# darpa-power-distribution.net
KiCad netlist of a schematic drawn in EAGLE
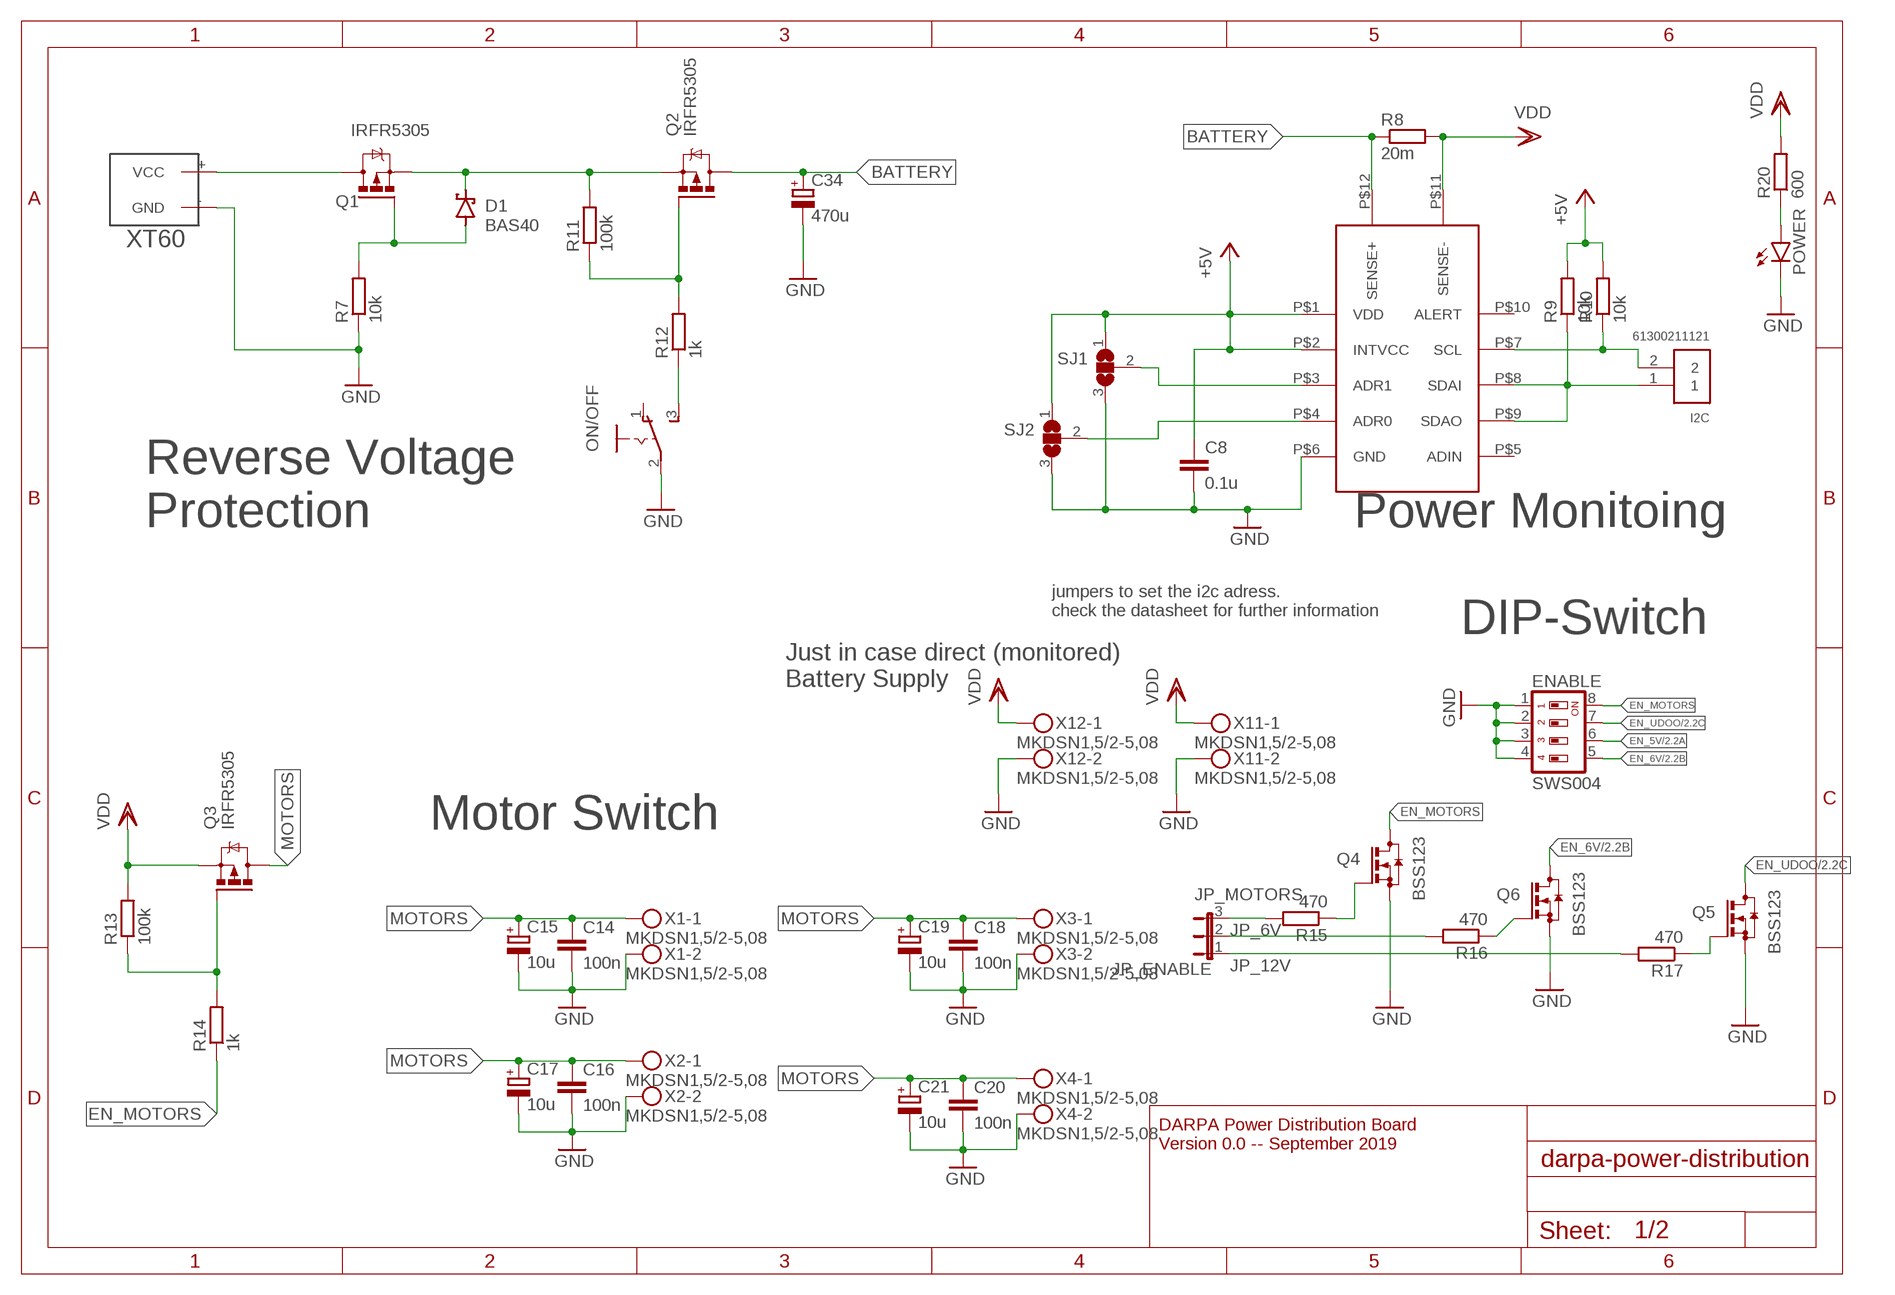
[diagram p0: schematic, sheet 1]
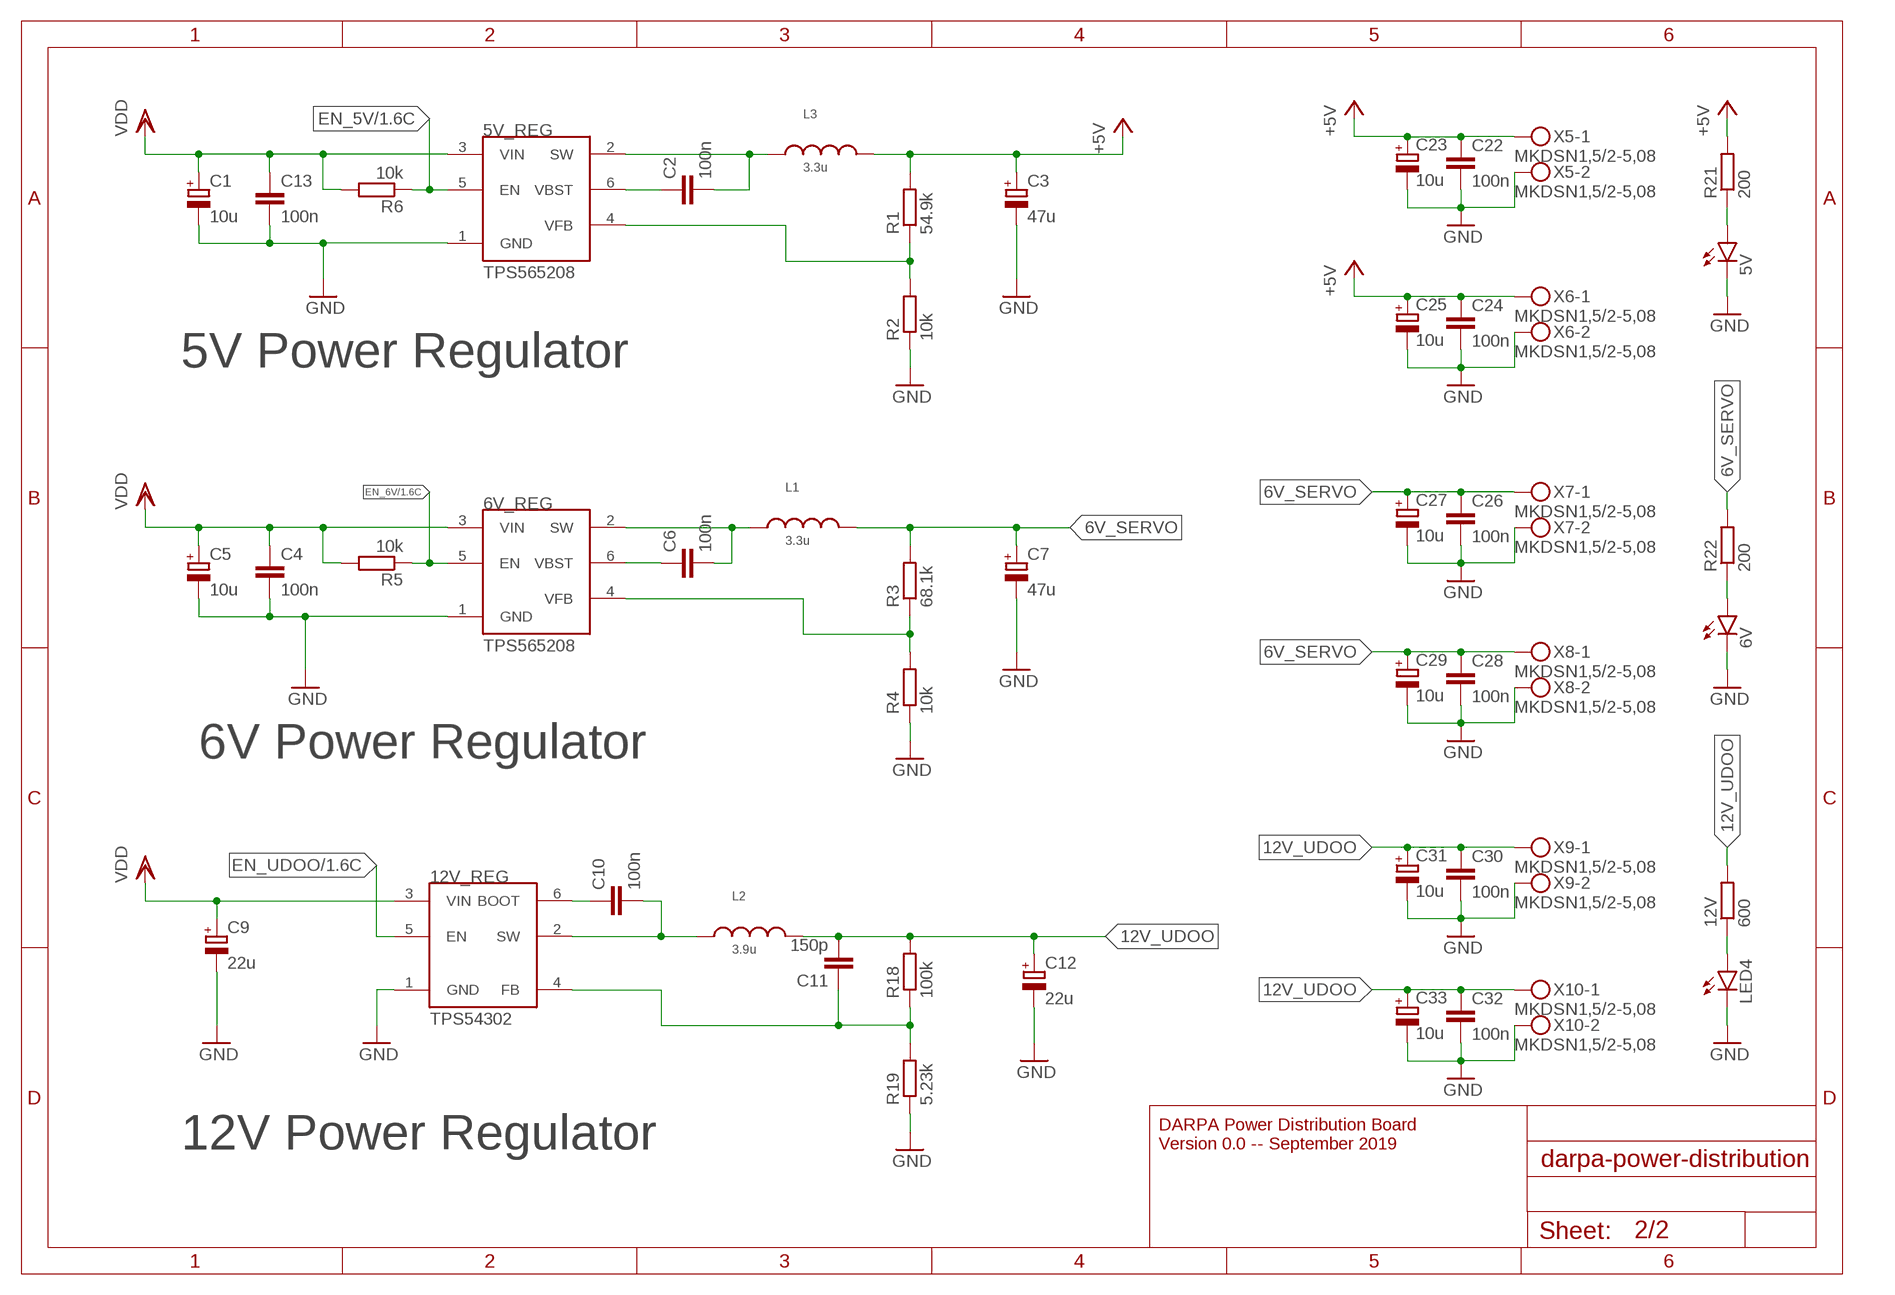
[diagram p1: schematic, sheet 2]

(export (version "E")
  (design (tool "Eeschema 10.0.6"))
  (components
    (comp (ref "C8")
      (value "0.1u")
      (footprint "eagle-import:C0805K")
      (libsource (lib "eagle-import") (part "C-EUC0805K"))
    )
    (comp (ref "C14")
      (value "100n")
      (footprint "eagle-import:C0805K")
      (libsource (lib "eagle-import") (part "C-EUC0805K"))
    )
    (comp (ref "C15")
      (value "10u")
      (footprint "eagle-import:E1,8-4")
      (libsource (lib "eagle-import") (part "CPOL-EUE1.8-4"))
    )
    (comp (ref "C16")
      (value "100n")
      (footprint "eagle-import:C0805K")
      (libsource (lib "eagle-import") (part "C-EUC0805K"))
    )
    (comp (ref "C17")
      (value "10u")
      (footprint "eagle-import:E1,8-4")
      (libsource (lib "eagle-import") (part "CPOL-EUE1.8-4"))
    )
    (comp (ref "C18")
      (value "100n")
      (footprint "eagle-import:C0805K")
      (libsource (lib "eagle-import") (part "C-EUC0805K"))
    )
    (comp (ref "C19")
      (value "10u")
      (footprint "eagle-import:E1,8-4")
      (libsource (lib "eagle-import") (part "CPOL-EUE1.8-4"))
    )
    (comp (ref "C20")
      (value "100n")
      (footprint "eagle-import:C0805K")
      (libsource (lib "eagle-import") (part "C-EUC0805K"))
    )
    (comp (ref "C21")
      (value "10u")
      (footprint "eagle-import:E1,8-4")
      (libsource (lib "eagle-import") (part "CPOL-EUE1.8-4"))
    )
    (comp (ref "C34")
      (value "470u")
      (footprint "eagle-import:E7,5-16")
      (libsource (lib "eagle-import") (part "CPOL-EUE7.5-16"))
    )
    (comp (ref "D1")
      (value "BAS40")
      (footprint "eagle-import:SOT23")
      (libsource (lib "eagle-import") (part "BAS40"))
    )
    (comp (ref "ENABLE")
      (value "SWS004")
      (footprint "eagle-import:SMS-004")
      (libsource (lib "eagle-import") (part "SWS004"))
    )
    (comp (ref "I2C")
      (value "61300211121")
      (footprint "eagle-import:61300211121")
      (fields
        (field (name "DIGI_KEY_PART_NUMBER") "732-5315-ND")
        (field (name "MANUFACTURER") "Wurth Electronics Inc.")
        (field (name "CREATED_BY") "PCBLayout.com")
      )
      (libsource (lib "eagle-import") (part "61300211121"))
    )
    (comp (ref "JP_ENABLE")
      (value "JP2E")
      (footprint "eagle-import:JP2")
      (libsource (lib "eagle-import") (part "JP2E"))
    )
    (comp (ref "ON/OFF")
      (value "M251")
      (footprint "eagle-import:M251")
      (libsource (lib "eagle-import") (part "M251"))
    )
    (comp (ref "POWER")
      (value "LEDSML0805")
      (footprint "eagle-import:SML0805")
      (libsource (lib "eagle-import") (part "LEDSML0805"))
    )
    (comp (ref "Q1")
      (value "IRFR5305")
      (footprint "eagle-import:D-PAK_TO252AA")
      (libsource (lib "eagle-import") (part "IRF?5305R"))
    )
    (comp (ref "Q2")
      (value "IRFR5305")
      (footprint "eagle-import:D-PAK_TO252AA")
      (libsource (lib "eagle-import") (part "IRF?5305R"))
    )
    (comp (ref "Q3")
      (value "IRFR5305")
      (footprint "eagle-import:D-PAK_TO252AA")
      (libsource (lib "eagle-import") (part "IRF?5305R"))
    )
    (comp (ref "Q4")
      (value "BSS123")
      (footprint "eagle-import:SOT23")
      (libsource (lib "eagle-import") (part "BSS123"))
    )
    (comp (ref "Q5")
      (value "BSS123")
      (footprint "eagle-import:SOT23")
      (libsource (lib "eagle-import") (part "BSS123"))
    )
    (comp (ref "Q6")
      (value "BSS123")
      (footprint "eagle-import:SOT23")
      (libsource (lib "eagle-import") (part "BSS123"))
    )
    (comp (ref "R7")
      (value "10k")
      (footprint "eagle-import:R0805")
      (libsource (lib "eagle-import") (part "R-EU_R0805"))
    )
    (comp (ref "R8")
      (value "20m")
      (footprint "eagle-import:P0613_15")
      (libsource (lib "eagle-import") (part "R-EU_0613/15"))
    )
    (comp (ref "R9")
      (value "10k")
      (footprint "eagle-import:R0805")
      (libsource (lib "eagle-import") (part "R-EU_R0805"))
    )
    (comp (ref "R10")
      (value "10k")
      (footprint "eagle-import:R0805")
      (libsource (lib "eagle-import") (part "R-EU_R0805"))
    )
    (comp (ref "R11")
      (value "100k")
      (footprint "eagle-import:R0805")
      (libsource (lib "eagle-import") (part "R-EU_R0805"))
    )
    (comp (ref "R12")
      (value "1k")
      (footprint "eagle-import:R0805")
      (libsource (lib "eagle-import") (part "R-EU_R0805"))
    )
    (comp (ref "R13")
      (value "100k")
      (footprint "eagle-import:R0805")
      (libsource (lib "eagle-import") (part "R-EU_R0805"))
    )
    (comp (ref "R14")
      (value "1k")
      (footprint "eagle-import:R0805")
      (libsource (lib "eagle-import") (part "R-EU_R0805"))
    )
    (comp (ref "R15")
      (value "470")
      (footprint "eagle-import:R0805")
      (libsource (lib "eagle-import") (part "R-EU_R0805"))
    )
    (comp (ref "R16")
      (value "470")
      (footprint "eagle-import:R0805")
      (libsource (lib "eagle-import") (part "R-EU_R0805"))
    )
    (comp (ref "R17")
      (value "470")
      (footprint "eagle-import:R0805")
      (libsource (lib "eagle-import") (part "R-EU_R0805"))
    )
    (comp (ref "R20")
      (value "600")
      (footprint "eagle-import:R0805")
      (libsource (lib "eagle-import") (part "R-EU_R0805"))
    )
    (comp (ref "SJ1")
      (value "SJ2W")
      (footprint "eagle-import:SJ_2")
      (libsource (lib "eagle-import") (part "SJ2W"))
    )
    (comp (ref "SJ2")
      (value "SJ2W")
      (footprint "eagle-import:SJ_2")
      (libsource (lib "eagle-import") (part "SJ2W"))
    )
    (comp (ref "U$3")
      (value "LTC2945")
      (footprint "eagle-import:LTC2945")
      (libsource (lib "eagle-import") (part "LTC2945"))
    )
    (comp (ref "U$4")
      (value "XT60")
      (footprint "eagle-import:XT60")
      (libsource (lib "eagle-import") (part "XT60"))
    )
    (comp (ref "X1")
      (value "MKDSN1,5/2-5,08")
      (footprint "eagle-import:MKDSN1,5_2-5,08")
      (libsource (lib "eagle-import") (part "MKDSN1,5/2-5,08"))
    )
    (comp (ref "X2")
      (value "MKDSN1,5/2-5,08")
      (footprint "eagle-import:MKDSN1,5_2-5,08")
      (libsource (lib "eagle-import") (part "MKDSN1,5/2-5,08"))
    )
    (comp (ref "X3")
      (value "MKDSN1,5/2-5,08")
      (footprint "eagle-import:MKDSN1,5_2-5,08")
      (libsource (lib "eagle-import") (part "MKDSN1,5/2-5,08"))
    )
    (comp (ref "X4")
      (value "MKDSN1,5/2-5,08")
      (footprint "eagle-import:MKDSN1,5_2-5,08")
      (libsource (lib "eagle-import") (part "MKDSN1,5/2-5,08"))
    )
    (comp (ref "X11")
      (value "MKDSN1,5/2-5,08")
      (footprint "eagle-import:MKDSN1,5_2-5,08")
      (libsource (lib "eagle-import") (part "MKDSN1,5/2-5,08"))
    )
    (comp (ref "X12")
      (value "MKDSN1,5/2-5,08")
      (footprint "eagle-import:MKDSN1,5_2-5,08")
      (libsource (lib "eagle-import") (part "MKDSN1,5/2-5,08"))
    )
    (comp (ref "5V")
      (value "LEDSML0805")
      (footprint "eagle-import:SML0805")
      (libsource (lib "eagle-import") (part "LEDSML0805"))
    )
    (comp (ref "5V_REG")
      (value "TPS565208")
      (footprint "eagle-import:SOT23-6")
      (libsource (lib "eagle-import") (part "TPS565208"))
    )
    (comp (ref "6V")
      (value "LEDSML0805")
      (footprint "eagle-import:SML0805")
      (libsource (lib "eagle-import") (part "LEDSML0805"))
    )
    (comp (ref "6V_REG")
      (value "TPS565208")
      (footprint "eagle-import:SOT23-6")
      (libsource (lib "eagle-import") (part "TPS565208"))
    )
    (comp (ref "12V")
      (value "600")
      (footprint "eagle-import:R0805")
      (libsource (lib "eagle-import") (part "R-EU_R0805"))
    )
    (comp (ref "12V_REG")
      (value "TPS54302")
      (footprint "eagle-import:SOT23-6")
      (libsource (lib "eagle-import") (part "TPS54302"))
    )
    (comp (ref "C1")
      (value "10u")
      (footprint "eagle-import:E1,8-4")
      (libsource (lib "eagle-import") (part "CPOL-EUE1.8-4"))
    )
    (comp (ref "C2")
      (value "100n")
      (footprint "eagle-import:C0805K")
      (libsource (lib "eagle-import") (part "C-EUC0805K"))
    )
    (comp (ref "C3")
      (value "47u")
      (footprint "eagle-import:E2,5-6")
      (libsource (lib "eagle-import") (part "CPOL-EUE2.5-6"))
    )
    (comp (ref "C4")
      (value "100n")
      (footprint "eagle-import:C0805K")
      (libsource (lib "eagle-import") (part "C-EUC0805K"))
    )
    (comp (ref "C5")
      (value "10u")
      (footprint "eagle-import:E1,8-4")
      (libsource (lib "eagle-import") (part "CPOL-EUE1.8-4"))
    )
    (comp (ref "C6")
      (value "100n")
      (footprint "eagle-import:C0805K")
      (libsource (lib "eagle-import") (part "C-EUC0805K"))
    )
    (comp (ref "C7")
      (value "47u")
      (footprint "eagle-import:E2,5-6")
      (libsource (lib "eagle-import") (part "CPOL-EUE2.5-6"))
    )
    (comp (ref "C9")
      (value "22u")
      (footprint "eagle-import:E2,5-6")
      (libsource (lib "eagle-import") (part "CPOL-EUE2.5-6"))
    )
    (comp (ref "C10")
      (value "100n")
      (footprint "eagle-import:C0805K")
      (libsource (lib "eagle-import") (part "C-EUC0805K"))
    )
    (comp (ref "C11")
      (value "150p")
      (footprint "eagle-import:C0805K")
      (libsource (lib "eagle-import") (part "C-EUC0805K"))
    )
    (comp (ref "C12")
      (value "22u")
      (footprint "eagle-import:E2,5-6")
      (libsource (lib "eagle-import") (part "CPOL-EUE2.5-6"))
    )
    (comp (ref "C13")
      (value "100n")
      (footprint "eagle-import:C0805K")
      (libsource (lib "eagle-import") (part "C-EUC0805K"))
    )
    (comp (ref "C22")
      (value "100n")
      (footprint "eagle-import:C0805K")
      (libsource (lib "eagle-import") (part "C-EUC0805K"))
    )
    (comp (ref "C23")
      (value "10u")
      (footprint "eagle-import:E1,8-4")
      (libsource (lib "eagle-import") (part "CPOL-EUE1.8-4"))
    )
    (comp (ref "C24")
      (value "100n")
      (footprint "eagle-import:C0805K")
      (libsource (lib "eagle-import") (part "C-EUC0805K"))
    )
    (comp (ref "C25")
      (value "10u")
      (footprint "eagle-import:E1,8-4")
      (libsource (lib "eagle-import") (part "CPOL-EUE1.8-4"))
    )
    (comp (ref "C26")
      (value "100n")
      (footprint "eagle-import:C0805K")
      (libsource (lib "eagle-import") (part "C-EUC0805K"))
    )
    (comp (ref "C27")
      (value "10u")
      (footprint "eagle-import:E1,8-4")
      (libsource (lib "eagle-import") (part "CPOL-EUE1.8-4"))
    )
    (comp (ref "C28")
      (value "100n")
      (footprint "eagle-import:C0805K")
      (libsource (lib "eagle-import") (part "C-EUC0805K"))
    )
    (comp (ref "C29")
      (value "10u")
      (footprint "eagle-import:E1,8-4")
      (libsource (lib "eagle-import") (part "CPOL-EUE1.8-4"))
    )
    (comp (ref "C30")
      (value "100n")
      (footprint "eagle-import:C0805K")
      (libsource (lib "eagle-import") (part "C-EUC0805K"))
    )
    (comp (ref "C31")
      (value "10u")
      (footprint "eagle-import:E1,8-4")
      (libsource (lib "eagle-import") (part "CPOL-EUE1.8-4"))
    )
    (comp (ref "C32")
      (value "100n")
      (footprint "eagle-import:C0805K")
      (libsource (lib "eagle-import") (part "C-EUC0805K"))
    )
    (comp (ref "C33")
      (value "10u")
      (footprint "eagle-import:E1,8-4")
      (libsource (lib "eagle-import") (part "CPOL-EUE1.8-4"))
    )
    (comp (ref "L1")
      (value "3.3u")
      (footprint "eagle-import:WE-CHSA_1011")
      (libsource (lib "eagle-import") (part "WE-CHSA_1011_7843330330"))
    )
    (comp (ref "L2")
      (value "3.9u")
      (footprint "eagle-import:WE-CHSA_1011")
      (libsource (lib "eagle-import") (part "WE-CHSA_1011_7843330330"))
    )
    (comp (ref "L3")
      (value "3.3u")
      (footprint "eagle-import:WE-CHSA_1011")
      (libsource (lib "eagle-import") (part "WE-CHSA_1011_7843330330"))
    )
    (comp (ref "LED4")
      (value "LEDSML0805")
      (footprint "eagle-import:SML0805")
      (libsource (lib "eagle-import") (part "LEDSML0805"))
    )
    (comp (ref "R1")
      (value "54.9k")
      (footprint "eagle-import:R0805")
      (libsource (lib "eagle-import") (part "R-EU_R0805"))
    )
    (comp (ref "R2")
      (value "10k")
      (footprint "eagle-import:R0805")
      (libsource (lib "eagle-import") (part "R-EU_R0805"))
    )
    (comp (ref "R3")
      (value "68.1k")
      (footprint "eagle-import:R0805")
      (libsource (lib "eagle-import") (part "R-EU_R0805"))
    )
    (comp (ref "R4")
      (value "10k")
      (footprint "eagle-import:R0805")
      (libsource (lib "eagle-import") (part "R-EU_R0805"))
    )
    (comp (ref "R5")
      (value "10k")
      (footprint "eagle-import:R0805")
      (libsource (lib "eagle-import") (part "R-EU_R0805"))
    )
    (comp (ref "R6")
      (value "10k")
      (footprint "eagle-import:R0805")
      (libsource (lib "eagle-import") (part "R-EU_R0805"))
    )
    (comp (ref "R18")
      (value "100k")
      (footprint "eagle-import:R0805")
      (libsource (lib "eagle-import") (part "R-EU_R0805"))
    )
    (comp (ref "R19")
      (value "5.23k")
      (footprint "eagle-import:R0805")
      (libsource (lib "eagle-import") (part "R-EU_R0805"))
    )
    (comp (ref "R21")
      (value "200")
      (footprint "eagle-import:R0805")
      (libsource (lib "eagle-import") (part "R-EU_R0805"))
    )
    (comp (ref "R22")
      (value "200")
      (footprint "eagle-import:R0805")
      (libsource (lib "eagle-import") (part "R-EU_R0805"))
    )
    (comp (ref "X5")
      (value "MKDSN1,5/2-5,08")
      (footprint "eagle-import:MKDSN1,5_2-5,08")
      (libsource (lib "eagle-import") (part "MKDSN1,5/2-5,08"))
    )
    (comp (ref "X6")
      (value "MKDSN1,5/2-5,08")
      (footprint "eagle-import:MKDSN1,5_2-5,08")
      (libsource (lib "eagle-import") (part "MKDSN1,5/2-5,08"))
    )
    (comp (ref "X7")
      (value "MKDSN1,5/2-5,08")
      (footprint "eagle-import:MKDSN1,5_2-5,08")
      (libsource (lib "eagle-import") (part "MKDSN1,5/2-5,08"))
    )
    (comp (ref "X8")
      (value "MKDSN1,5/2-5,08")
      (footprint "eagle-import:MKDSN1,5_2-5,08")
      (libsource (lib "eagle-import") (part "MKDSN1,5/2-5,08"))
    )
    (comp (ref "X9")
      (value "MKDSN1,5/2-5,08")
      (footprint "eagle-import:MKDSN1,5_2-5,08")
      (libsource (lib "eagle-import") (part "MKDSN1,5/2-5,08"))
    )
    (comp (ref "X10")
      (value "MKDSN1,5/2-5,08")
      (footprint "eagle-import:MKDSN1,5_2-5,08")
      (libsource (lib "eagle-import") (part "MKDSN1,5/2-5,08"))
    )
  )
  (nets
    (net (code "1") (name "+5V") (class "Default")
      (node (ref "C22") (pin "1") (pinfunction "1_1") (pintype "passive"))
      (node (ref "C23") (pin "+") (pinfunction "+_+") (pintype "passive"))
      (node (ref "C24") (pin "1") (pinfunction "1_1") (pintype "passive"))
      (node (ref "C25") (pin "+") (pinfunction "+_+") (pintype "passive"))
      (node (ref "C3") (pin "+") (pinfunction "+_+") (pintype "passive"))
      (node (ref "C8") (pin "1") (pinfunction "1_1") (pintype "passive"))
      (node (ref "L3") (pin "2") (pinfunction "2_2") (pintype "passive"))
      (node (ref "R1") (pin "2") (pinfunction "2_2") (pintype "passive"))
      (node (ref "R10") (pin "2") (pinfunction "2_2") (pintype "passive"))
      (node (ref "R21") (pin "2") (pinfunction "2_2") (pintype "passive"))
      (node (ref "R9") (pin "2") (pinfunction "2_2") (pintype "passive"))
      (node (ref "SJ1") (pin "1") (pinfunction "1_1") (pintype "passive"))
      (node (ref "SJ2") (pin "1") (pinfunction "1_1") (pintype "passive"))
      (node (ref "U$3") (pin "P$1") (pinfunction "VDD_P$1") (pintype "bidirectional"))
      (node (ref "U$3") (pin "P$2") (pinfunction "INTVCC_P$2") (pintype "bidirectional"))
      (node (ref "X5") (pin "1") (pinfunction "KL_1") (pintype "passive"))
      (node (ref "X6") (pin "1") (pinfunction "KL_1") (pintype "passive"))
    )
    (net (code "2") (name "6V_SERVO") (class "Default")
      (node (ref "C26") (pin "1") (pinfunction "1_1") (pintype "passive"))
      (node (ref "C27") (pin "+") (pinfunction "+_+") (pintype "passive"))
      (node (ref "C28") (pin "1") (pinfunction "1_1") (pintype "passive"))
      (node (ref "C29") (pin "+") (pinfunction "+_+") (pintype "passive"))
      (node (ref "C7") (pin "+") (pinfunction "+_+") (pintype "passive"))
      (node (ref "L1") (pin "2") (pinfunction "2_2") (pintype "passive"))
      (node (ref "R22") (pin "2") (pinfunction "2_2") (pintype "passive"))
      (node (ref "R3") (pin "2") (pinfunction "2_2") (pintype "passive"))
      (node (ref "X7") (pin "1") (pinfunction "KL_1") (pintype "passive"))
      (node (ref "X8") (pin "1") (pinfunction "KL_1") (pintype "passive"))
    )
    (net (code "3") (name "12V_UDOO") (class "Default")
      (node (ref "12V") (pin "2") (pinfunction "2_2") (pintype "passive"))
      (node (ref "C11") (pin "2") (pinfunction "2_2") (pintype "passive"))
      (node (ref "C12") (pin "+") (pinfunction "+_+") (pintype "passive"))
      (node (ref "C30") (pin "1") (pinfunction "1_1") (pintype "passive"))
      (node (ref "C31") (pin "+") (pinfunction "+_+") (pintype "passive"))
      (node (ref "C32") (pin "1") (pinfunction "1_1") (pintype "passive"))
      (node (ref "C33") (pin "+") (pinfunction "+_+") (pintype "passive"))
      (node (ref "L2") (pin "2") (pinfunction "2_2") (pintype "passive"))
      (node (ref "R18") (pin "2") (pinfunction "2_2") (pintype "passive"))
      (node (ref "X10") (pin "1") (pinfunction "KL_1") (pintype "passive"))
      (node (ref "X9") (pin "1") (pinfunction "KL_1") (pintype "passive"))
    )
    (net (code "4") (name "BATTERY") (class "Default")
      (node (ref "C34") (pin "+") (pinfunction "+_+") (pintype "passive"))
      (node (ref "Q2") (pin "4") (pinfunction "D_4") (pintype "passive"))
      (node (ref "R8") (pin "1") (pinfunction "1_1") (pintype "passive"))
      (node (ref "U$3") (pin "P$12") (pinfunction "SENSE+_P$12") (pintype "bidirectional"))
    )
    (net (code "5") (name "EN_5V") (class "Default")
      (node (ref "5V_REG") (pin "5") (pinfunction "EN_5") (pintype "bidirectional"))
      (node (ref "ENABLE") (pin "6") (pinfunction "6_6") (pintype "passive"))
      (node (ref "R6") (pin "1") (pinfunction "1_1") (pintype "passive"))
    )
    (net (code "6") (name "EN_6V") (class "Default")
      (node (ref "6V_REG") (pin "5") (pinfunction "EN_5") (pintype "bidirectional"))
      (node (ref "ENABLE") (pin "5") (pinfunction "5_5") (pintype "passive"))
      (node (ref "Q6") (pin "3") (pinfunction "D_3") (pintype "passive"))
      (node (ref "R5") (pin "1") (pinfunction "1_1") (pintype "passive"))
    )
    (net (code "7") (name "EN_MOTORS") (class "Default")
      (node (ref "ENABLE") (pin "8") (pinfunction "8_8") (pintype "passive"))
      (node (ref "Q4") (pin "3") (pinfunction "D_3") (pintype "passive"))
      (node (ref "R14") (pin "1") (pinfunction "1_1") (pintype "passive"))
    )
    (net (code "8") (name "EN_UDOO") (class "Default")
      (node (ref "12V_REG") (pin "5") (pinfunction "EN_5") (pintype "bidirectional"))
      (node (ref "ENABLE") (pin "7") (pinfunction "7_7") (pintype "passive"))
      (node (ref "Q5") (pin "3") (pinfunction "D_3") (pintype "passive"))
    )
    (net (code "9") (name "GND") (class "Default")
      (node (ref "12V_REG") (pin "1") (pinfunction "GND_1") (pintype "bidirectional"))
      (node (ref "5V") (pin "C") (pinfunction "C_C") (pintype "passive"))
      (node (ref "5V_REG") (pin "1") (pinfunction "GND_1") (pintype "bidirectional"))
      (node (ref "6V") (pin "C") (pinfunction "C_C") (pintype "passive"))
      (node (ref "6V_REG") (pin "1") (pinfunction "GND_1") (pintype "bidirectional"))
      (node (ref "C1") (pin "-") (pinfunction "-_-") (pintype "passive"))
      (node (ref "C12") (pin "-") (pinfunction "-_-") (pintype "passive"))
      (node (ref "C13") (pin "2") (pinfunction "2_2") (pintype "passive"))
      (node (ref "C14") (pin "2") (pinfunction "2_2") (pintype "passive"))
      (node (ref "C15") (pin "-") (pinfunction "-_-") (pintype "passive"))
      (node (ref "C16") (pin "2") (pinfunction "2_2") (pintype "passive"))
      (node (ref "C17") (pin "-") (pinfunction "-_-") (pintype "passive"))
      (node (ref "C18") (pin "2") (pinfunction "2_2") (pintype "passive"))
      (node (ref "C19") (pin "-") (pinfunction "-_-") (pintype "passive"))
      (node (ref "C20") (pin "2") (pinfunction "2_2") (pintype "passive"))
      (node (ref "C21") (pin "-") (pinfunction "-_-") (pintype "passive"))
      (node (ref "C22") (pin "2") (pinfunction "2_2") (pintype "passive"))
      (node (ref "C23") (pin "-") (pinfunction "-_-") (pintype "passive"))
      (node (ref "C24") (pin "2") (pinfunction "2_2") (pintype "passive"))
      (node (ref "C25") (pin "-") (pinfunction "-_-") (pintype "passive"))
      (node (ref "C26") (pin "2") (pinfunction "2_2") (pintype "passive"))
      (node (ref "C27") (pin "-") (pinfunction "-_-") (pintype "passive"))
      (node (ref "C28") (pin "2") (pinfunction "2_2") (pintype "passive"))
      (node (ref "C29") (pin "-") (pinfunction "-_-") (pintype "passive"))
      (node (ref "C3") (pin "-") (pinfunction "-_-") (pintype "passive"))
      (node (ref "C30") (pin "2") (pinfunction "2_2") (pintype "passive"))
      (node (ref "C31") (pin "-") (pinfunction "-_-") (pintype "passive"))
      (node (ref "C32") (pin "2") (pinfunction "2_2") (pintype "passive"))
      (node (ref "C33") (pin "-") (pinfunction "-_-") (pintype "passive"))
      (node (ref "C34") (pin "-") (pinfunction "-_-") (pintype "passive"))
      (node (ref "C4") (pin "2") (pinfunction "2_2") (pintype "passive"))
      (node (ref "C5") (pin "-") (pinfunction "-_-") (pintype "passive"))
      (node (ref "C7") (pin "-") (pinfunction "-_-") (pintype "passive"))
      (node (ref "C8") (pin "2") (pinfunction "2_2") (pintype "passive"))
      (node (ref "C9") (pin "-") (pinfunction "-_-") (pintype "passive"))
      (node (ref "ENABLE") (pin "1") (pinfunction "1_1") (pintype "passive"))
      (node (ref "ENABLE") (pin "2") (pinfunction "2_2") (pintype "passive"))
      (node (ref "ENABLE") (pin "3") (pinfunction "3_3") (pintype "passive"))
      (node (ref "ENABLE") (pin "4") (pinfunction "4_4") (pintype "passive"))
      (node (ref "LED4") (pin "C") (pinfunction "C_C") (pintype "passive"))
      (node (ref "ON/OFF") (pin "2") (pinfunction "P_2") (pintype "passive"))
      (node (ref "POWER") (pin "C") (pinfunction "C_C") (pintype "passive"))
      (node (ref "Q4") (pin "2") (pinfunction "S_2") (pintype "passive"))
      (node (ref "Q5") (pin "2") (pinfunction "S_2") (pintype "passive"))
      (node (ref "Q6") (pin "2") (pinfunction "S_2") (pintype "passive"))
      (node (ref "R19") (pin "1") (pinfunction "1_1") (pintype "passive"))
      (node (ref "R2") (pin "1") (pinfunction "1_1") (pintype "passive"))
      (node (ref "R4") (pin "1") (pinfunction "1_1") (pintype "passive"))
      (node (ref "R7") (pin "1") (pinfunction "1_1") (pintype "passive"))
      (node (ref "SJ1") (pin "3") (pinfunction "3_3") (pintype "passive"))
      (node (ref "SJ2") (pin "3") (pinfunction "3_3") (pintype "passive"))
      (node (ref "U$3") (pin "P$6") (pinfunction "GND_P$6") (pintype "bidirectional"))
      (node (ref "U$4") (pin "-") (pinfunction "GND_-") (pintype "bidirectional"))
      (node (ref "X1") (pin "2") (pinfunction "KL_2") (pintype "passive"))
      (node (ref "X10") (pin "2") (pinfunction "KL_2") (pintype "passive"))
      (node (ref "X11") (pin "2") (pinfunction "KL_2") (pintype "passive"))
      (node (ref "X12") (pin "2") (pinfunction "KL_2") (pintype "passive"))
      (node (ref "X2") (pin "2") (pinfunction "KL_2") (pintype "passive"))
      (node (ref "X3") (pin "2") (pinfunction "KL_2") (pintype "passive"))
      (node (ref "X4") (pin "2") (pinfunction "KL_2") (pintype "passive"))
      (node (ref "X5") (pin "2") (pinfunction "KL_2") (pintype "passive"))
      (node (ref "X6") (pin "2") (pinfunction "KL_2") (pintype "passive"))
      (node (ref "X7") (pin "2") (pinfunction "KL_2") (pintype "passive"))
      (node (ref "X8") (pin "2") (pinfunction "KL_2") (pintype "passive"))
      (node (ref "X9") (pin "2") (pinfunction "KL_2") (pintype "passive"))
    )
    (net (code "10") (name "JP_6V") (class "Default")
      (node (ref "JP_ENABLE") (pin "2") (pinfunction "2_2") (pintype "passive"))
      (node (ref "R16") (pin "2") (pinfunction "2_2") (pintype "passive"))
    )
    (net (code "11") (name "JP_12V") (class "Default")
      (node (ref "JP_ENABLE") (pin "1") (pinfunction "1_1") (pintype "passive"))
      (node (ref "R17") (pin "2") (pinfunction "2_2") (pintype "passive"))
    )
    (net (code "12") (name "JP_MOTORS") (class "Default")
      (node (ref "JP_ENABLE") (pin "3") (pinfunction "3_3") (pintype "passive"))
      (node (ref "R15") (pin "2") (pinfunction "2_2") (pintype "passive"))
    )
    (net (code "13") (name "MOTORS") (class "Default")
      (node (ref "C14") (pin "1") (pinfunction "1_1") (pintype "passive"))
      (node (ref "C15") (pin "+") (pinfunction "+_+") (pintype "passive"))
      (node (ref "C16") (pin "1") (pinfunction "1_1") (pintype "passive"))
      (node (ref "C17") (pin "+") (pinfunction "+_+") (pintype "passive"))
      (node (ref "C18") (pin "1") (pinfunction "1_1") (pintype "passive"))
      (node (ref "C19") (pin "+") (pinfunction "+_+") (pintype "passive"))
      (node (ref "C20") (pin "1") (pinfunction "1_1") (pintype "passive"))
      (node (ref "C21") (pin "+") (pinfunction "+_+") (pintype "passive"))
      (node (ref "Q3") (pin "4") (pinfunction "D_4") (pintype "passive"))
      (node (ref "X1") (pin "1") (pinfunction "KL_1") (pintype "passive"))
      (node (ref "X2") (pin "1") (pinfunction "KL_1") (pintype "passive"))
      (node (ref "X3") (pin "1") (pinfunction "KL_1") (pintype "passive"))
      (node (ref "X4") (pin "1") (pinfunction "KL_1") (pintype "passive"))
    )
    (net (code "14") (name "Net-(5V-PadA)") (class "Default")
      (node (ref "5V") (pin "A") (pinfunction "A_A") (pintype "passive"))
      (node (ref "R21") (pin "1") (pinfunction "1_1") (pintype "passive"))
    )
    (net (code "15") (name "Net-(5V_REG-SW)") (class "Default")
      (node (ref "5V_REG") (pin "2") (pinfunction "SW_2") (pintype "bidirectional"))
      (node (ref "C2") (pin "2") (pinfunction "2_2") (pintype "passive"))
      (node (ref "L3") (pin "1") (pinfunction "1_1") (pintype "passive"))
    )
    (net (code "16") (name "Net-(5V_REG-VBST)") (class "Default")
      (node (ref "5V_REG") (pin "6") (pinfunction "VBST_6") (pintype "bidirectional"))
      (node (ref "C2") (pin "1") (pinfunction "1_1") (pintype "passive"))
    )
    (net (code "17") (name "Net-(5V_REG-VFB)") (class "Default")
      (node (ref "5V_REG") (pin "4") (pinfunction "VFB_4") (pintype "bidirectional"))
      (node (ref "R1") (pin "1") (pinfunction "1_1") (pintype "passive"))
      (node (ref "R2") (pin "2") (pinfunction "2_2") (pintype "passive"))
    )
    (net (code "18") (name "Net-(6V-PadA)") (class "Default")
      (node (ref "6V") (pin "A") (pinfunction "A_A") (pintype "passive"))
      (node (ref "R22") (pin "1") (pinfunction "1_1") (pintype "passive"))
    )
    (net (code "19") (name "Net-(6V_REG-SW)") (class "Default")
      (node (ref "6V_REG") (pin "2") (pinfunction "SW_2") (pintype "bidirectional"))
      (node (ref "C6") (pin "2") (pinfunction "2_2") (pintype "passive"))
      (node (ref "L1") (pin "1") (pinfunction "1_1") (pintype "passive"))
    )
    (net (code "20") (name "Net-(6V_REG-VBST)") (class "Default")
      (node (ref "6V_REG") (pin "6") (pinfunction "VBST_6") (pintype "bidirectional"))
      (node (ref "C6") (pin "1") (pinfunction "1_1") (pintype "passive"))
    )
    (net (code "21") (name "Net-(6V_REG-VFB)") (class "Default")
      (node (ref "6V_REG") (pin "4") (pinfunction "VFB_4") (pintype "bidirectional"))
      (node (ref "R3") (pin "1") (pinfunction "1_1") (pintype "passive"))
      (node (ref "R4") (pin "2") (pinfunction "2_2") (pintype "passive"))
    )
    (net (code "22") (name "Net-(12V-Pad1)") (class "Default")
      (node (ref "12V") (pin "1") (pinfunction "1_1") (pintype "passive"))
      (node (ref "LED4") (pin "A") (pinfunction "A_A") (pintype "passive"))
    )
    (net (code "23") (name "Net-(12V_REG-BOOT)") (class "Default")
      (node (ref "12V_REG") (pin "6") (pinfunction "BOOT_6") (pintype "bidirectional"))
      (node (ref "C10") (pin "1") (pinfunction "1_1") (pintype "passive"))
    )
    (net (code "24") (name "Net-(12V_REG-FB)") (class "Default")
      (node (ref "12V_REG") (pin "4") (pinfunction "FB_4") (pintype "bidirectional"))
      (node (ref "C11") (pin "1") (pinfunction "1_1") (pintype "passive"))
      (node (ref "R18") (pin "1") (pinfunction "1_1") (pintype "passive"))
      (node (ref "R19") (pin "2") (pinfunction "2_2") (pintype "passive"))
    )
    (net (code "25") (name "Net-(12V_REG-SW)") (class "Default")
      (node (ref "12V_REG") (pin "2") (pinfunction "SW_2") (pintype "bidirectional"))
      (node (ref "C10") (pin "2") (pinfunction "2_2") (pintype "passive"))
      (node (ref "L2") (pin "1") (pinfunction "1_1") (pintype "passive"))
    )
    (net (code "26") (name "Net-(D1-A)") (class "Default")
      (node (ref "D1") (pin "1") (pinfunction "A_1") (pintype "passive"))
      (node (ref "Q1") (pin "1") (pinfunction "G_1") (pintype "passive"))
      (node (ref "R7") (pin "2") (pinfunction "2_2") (pintype "passive"))
    )
    (net (code "27") (name "Net-(D1-C)") (class "Default")
      (node (ref "D1") (pin "3") (pinfunction "C_3") (pintype "passive"))
      (node (ref "Q1") (pin "3") (pinfunction "S_3") (pintype "passive"))
      (node (ref "Q2") (pin "3") (pinfunction "S_3") (pintype "passive"))
      (node (ref "R11") (pin "2") (pinfunction "2_2") (pintype "passive"))
    )
    (net (code "28") (name "Net-(ON/OFF-S)") (class "Default")
      (node (ref "ON/OFF") (pin "3") (pinfunction "S_3") (pintype "passive"))
      (node (ref "R12") (pin "1") (pinfunction "1_1") (pintype "passive"))
    )
    (net (code "29") (name "Net-(POWER-PadA)") (class "Default")
      (node (ref "POWER") (pin "A") (pinfunction "A_A") (pintype "passive"))
      (node (ref "R20") (pin "1") (pinfunction "1_1") (pintype "passive"))
    )
    (net (code "30") (name "Net-(Q1-D)") (class "Default")
      (node (ref "Q1") (pin "4") (pinfunction "D_4") (pintype "passive"))
      (node (ref "U$4") (pin "+") (pinfunction "VCC_+") (pintype "bidirectional"))
    )
    (net (code "31") (name "Net-(Q2-G)") (class "Default")
      (node (ref "Q2") (pin "1") (pinfunction "G_1") (pintype "passive"))
      (node (ref "R11") (pin "1") (pinfunction "1_1") (pintype "passive"))
      (node (ref "R12") (pin "2") (pinfunction "2_2") (pintype "passive"))
    )
    (net (code "32") (name "Net-(Q3-G)") (class "Default")
      (node (ref "Q3") (pin "1") (pinfunction "G_1") (pintype "passive"))
      (node (ref "R13") (pin "1") (pinfunction "1_1") (pintype "passive"))
      (node (ref "R14") (pin "2") (pinfunction "2_2") (pintype "passive"))
    )
    (net (code "33") (name "Net-(Q4-G)") (class "Default")
      (node (ref "Q4") (pin "1") (pinfunction "G_1") (pintype "passive"))
      (node (ref "R15") (pin "1") (pinfunction "1_1") (pintype "passive"))
    )
    (net (code "34") (name "Net-(Q5-G)") (class "Default")
      (node (ref "Q5") (pin "1") (pinfunction "G_1") (pintype "passive"))
      (node (ref "R17") (pin "1") (pinfunction "1_1") (pintype "passive"))
    )
    (net (code "35") (name "Net-(Q6-G)") (class "Default")
      (node (ref "Q6") (pin "1") (pinfunction "G_1") (pintype "passive"))
      (node (ref "R16") (pin "1") (pinfunction "1_1") (pintype "passive"))
    )
    (net (code "36") (name "Net-(U$3-ADR0)") (class "Default")
      (node (ref "SJ2") (pin "2") (pinfunction "2_2") (pintype "passive"))
      (node (ref "U$3") (pin "P$4") (pinfunction "ADR0_P$4") (pintype "bidirectional"))
    )
    (net (code "37") (name "Net-(U$3-ADR1)") (class "Default")
      (node (ref "SJ1") (pin "2") (pinfunction "2_2") (pintype "passive"))
      (node (ref "U$3") (pin "P$3") (pinfunction "ADR1_P$3") (pintype "bidirectional"))
    )
    (net (code "38") (name "Net-(U$3-SCL)") (class "Default")
      (node (ref "I2C") (pin "2") (pinfunction "2_2") (pintype "passive"))
      (node (ref "R10") (pin "1") (pinfunction "1_1") (pintype "passive"))
      (node (ref "U$3") (pin "P$7") (pinfunction "SCL_P$7") (pintype "bidirectional"))
    )
    (net (code "39") (name "Net-(U$3-SDAI)") (class "Default")
      (node (ref "I2C") (pin "1") (pinfunction "1_1") (pintype "passive"))
      (node (ref "R9") (pin "1") (pinfunction "1_1") (pintype "passive"))
      (node (ref "U$3") (pin "P$8") (pinfunction "SDAI_P$8") (pintype "bidirectional"))
      (node (ref "U$3") (pin "P$9") (pinfunction "SDAO_P$9") (pintype "bidirectional"))
    )
    (net (code "40") (name "VDD") (class "Default")
      (node (ref "12V_REG") (pin "3") (pinfunction "VIN_3") (pintype "bidirectional"))
      (node (ref "5V_REG") (pin "3") (pinfunction "VIN_3") (pintype "bidirectional"))
      (node (ref "6V_REG") (pin "3") (pinfunction "VIN_3") (pintype "bidirectional"))
      (node (ref "C1") (pin "+") (pinfunction "+_+") (pintype "passive"))
      (node (ref "C13") (pin "1") (pinfunction "1_1") (pintype "passive"))
      (node (ref "C4") (pin "1") (pinfunction "1_1") (pintype "passive"))
      (node (ref "C5") (pin "+") (pinfunction "+_+") (pintype "passive"))
      (node (ref "C9") (pin "+") (pinfunction "+_+") (pintype "passive"))
      (node (ref "Q3") (pin "3") (pinfunction "S_3") (pintype "passive"))
      (node (ref "R13") (pin "2") (pinfunction "2_2") (pintype "passive"))
      (node (ref "R20") (pin "2") (pinfunction "2_2") (pintype "passive"))
      (node (ref "R5") (pin "2") (pinfunction "2_2") (pintype "passive"))
      (node (ref "R6") (pin "2") (pinfunction "2_2") (pintype "passive"))
      (node (ref "R8") (pin "2") (pinfunction "2_2") (pintype "passive"))
      (node (ref "U$3") (pin "P$11") (pinfunction "SENSE-_P$11") (pintype "bidirectional"))
      (node (ref "X11") (pin "1") (pinfunction "KL_1") (pintype "passive"))
      (node (ref "X12") (pin "1") (pinfunction "KL_1") (pintype "passive"))
    )
    (net (code "41") (name "unconnected-(ON/OFF-O-Pad1)") (class "Default")
      (node (ref "ON/OFF") (pin "1") (pinfunction "O_1") (pintype "passive"))
    )
    (net (code "42") (name "unconnected-(U$3-ADIN-PadP$5)") (class "Default")
      (node (ref "U$3") (pin "P$5") (pinfunction "ADIN_P$5") (pintype "bidirectional"))
    )
    (net (code "43") (name "unconnected-(U$3-ALERT-PadP$10)") (class "Default")
      (node (ref "U$3") (pin "P$10") (pinfunction "ALERT_P$10") (pintype "bidirectional"))
    )
  )
)
